# ESP32__20240824.net
KiCad netlist of a schematic drawn in Altium Designer
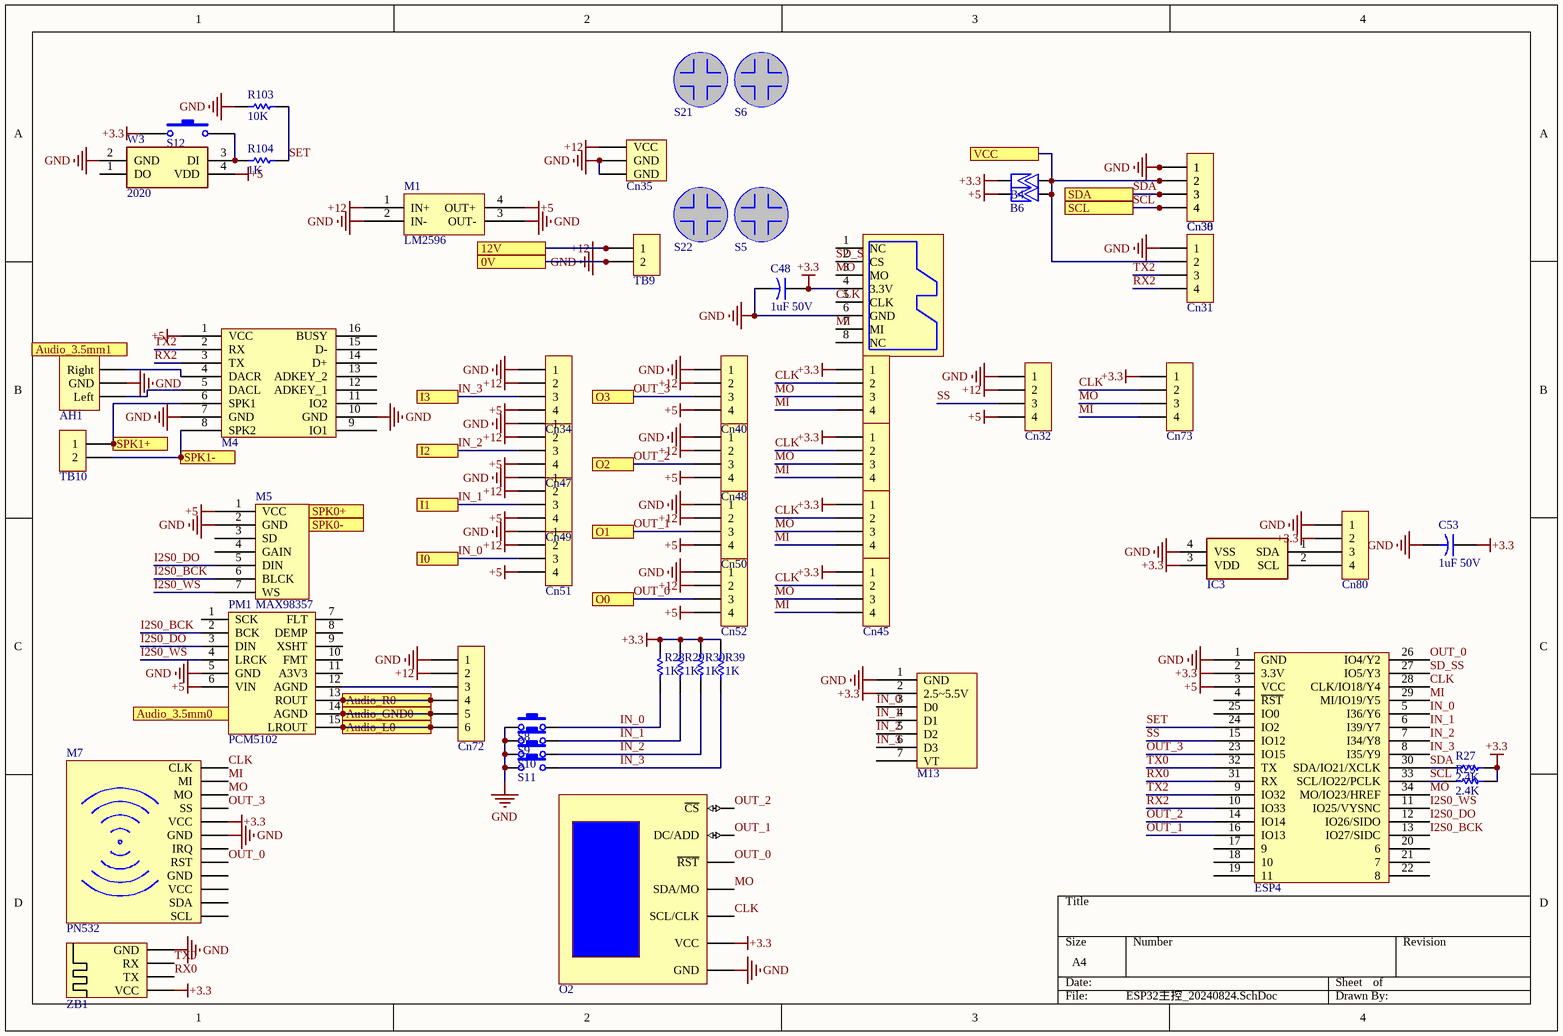
[diagram p0: ESP32主控_20240824.SchDoc]

(export (version "E")
  (design (tool "Eeschema 10.0.6"))
  (components
    (comp (ref "AH1")
      (value "Interface_Audio_hole")
      (footprint "Audio_hole_DIP")
      (description "音源孔")
      (libsource (lib "MyLibray") (part "Interface_Audio_hole"))
    )
    (comp (ref "B4")
      (value "短路")
      (footprint "BYPASS-0805")
      (description "短路焊點(如標註短路則需額外補錫使其短路)")
      (libsource (lib "MyLibray") (part "Bypass"))
    )
    (comp (ref "B6")
      (value "不短路")
      (footprint "BYPASS-0805")
      (description "短路焊點(如標註短路則需額外補錫使其短路)")
      (libsource (lib "MyLibray") (part "Bypass"))
    )
    (comp (ref "C48")
      (value "1uF 50V")
      (footprint "Cap-1206")
      (description "電容")
      (libsource (lib "MyLibray") (part "Cap"))
    )
    (comp (ref "C53")
      (value "1uF 50V")
      (footprint "Cap-1206")
      (description "電容")
      (libsource (lib "MyLibray") (part "Cap"))
    )
    (comp (ref "Cn28")
      (value "KF2510")
      (footprint "Connector_KF2510-4A")
      (description "接線端子")
      (libsource (lib "MyLibray") (part "Contact(4P)"))
    )
    (comp (ref "Cn29")
      (value "KF2510")
      (footprint "Connector_KF2510-4A")
      (description "接線端子")
      (libsource (lib "MyLibray") (part "Contact(4P)"))
    )
    (comp (ref "Cn30")
      (value "KF2510")
      (footprint "Connector_KF2510-4A")
      (description "接線端子")
      (libsource (lib "MyLibray") (part "Contact(4P)"))
    )
    (comp (ref "Cn31")
      (value "KF2510")
      (footprint "Connector_KF2510-4A")
      (description "接線端子")
      (libsource (lib "MyLibray") (part "Contact(4P)"))
    )
    (comp (ref "Cn32")
      (value "KF2510")
      (footprint "Connector_KF2510-4A")
      (description "接線端子")
      (libsource (lib "MyLibray") (part "Contact(4P)"))
    )
    (comp (ref "Cn34")
      (value "KF2510")
      (footprint "Connector_KF2510-4A")
      (description "接線端子")
      (libsource (lib "MyLibray") (part "Contact(4P)"))
    )
    (comp (ref "Cn35")
      (value "DC-005")
      (footprint "Connector_DC-005")
      (description "DC直流接頭")
      (libsource (lib "MyLibray") (part "Contact_DC"))
    )
    (comp (ref "Cn38")
      (value "KF2510")
      (footprint "Connector_KF2510-4A")
      (description "接線端子")
      (libsource (lib "MyLibray") (part "Contact(4P)"))
    )
    (comp (ref "Cn40")
      (value "KF2510")
      (footprint "Connector_KF2510-4A")
      (description "接線端子")
      (libsource (lib "MyLibray") (part "Contact(4P)"))
    )
    (comp (ref "Cn43")
      (value "KF2510")
      (footprint "Connector_KF2510-4A")
      (description "接線端子")
      (libsource (lib "MyLibray") (part "Contact(4P)"))
    )
    (comp (ref "Cn45")
      (value "KF2510")
      (footprint "Connector_KF2510-4A")
      (description "接線端子")
      (libsource (lib "MyLibray") (part "Contact(4P)"))
    )
    (comp (ref "Cn47")
      (value "KF2510")
      (footprint "Connector_KF2510-4A")
      (description "接線端子")
      (libsource (lib "MyLibray") (part "Contact(4P)"))
    )
    (comp (ref "Cn48")
      (value "KF2510")
      (footprint "Connector_KF2510-4A")
      (description "接線端子")
      (libsource (lib "MyLibray") (part "Contact(4P)"))
    )
    (comp (ref "Cn49")
      (value "KF2510")
      (footprint "Connector_KF2510-4A")
      (description "接線端子")
      (libsource (lib "MyLibray") (part "Contact(4P)"))
    )
    (comp (ref "Cn50")
      (value "KF2510")
      (footprint "Connector_KF2510-4A")
      (description "接線端子")
      (libsource (lib "MyLibray") (part "Contact(4P)"))
    )
    (comp (ref "Cn51")
      (value "KF2510")
      (footprint "Connector_KF2510-4A")
      (description "接線端子")
      (libsource (lib "MyLibray") (part "Contact(4P)"))
    )
    (comp (ref "Cn52")
      (value "KF2510")
      (footprint "Connector_KF2510-4A")
      (description "接線端子")
      (libsource (lib "MyLibray") (part "Contact(4P)"))
    )
    (comp (ref "Cn72")
      (value "KF2510-6")
      (footprint "Connector_KF2510-6W")
      (description "接線端子")
      (libsource (lib "MyLibray") (part "Contact(6P)"))
    )
    (comp (ref "Cn73")
      (value "KF2510")
      (footprint "Connector_KF2510-4A")
      (description "接線端子")
      (libsource (lib "MyLibray") (part "Contact(4P)"))
    )
    (comp (ref "Cn80")
      (value "KF2510")
      (footprint "Connector_KF2510-4A")
      (description "接線端子")
      (libsource (lib "MyLibray") (part "Contact(4P)"))
    )
    (comp (ref "ESP4")
      (value "U?")
      (footprint "ESP32-WROVER-CAM Module")
      (description "WIFI通訊模組,帶OV2640攝像頭")
      (libsource (lib "MyModule") (part "ESP32-WROVER-CAM"))
    )
    (comp (ref "IC3")
      (value "SHT40")
      (footprint "Sensor_SHT40")
      (description "I2C,溫溼度感測器")
      (fields (field (name "MANUFACTURER_PART_NUMBER") "SHT40-AD1B-R3"))
      (libsource (lib "MyLibray") (part "Sensor_SHT40-AD1B-R3"))
    )
    (comp (ref "M1")
      (value "LM2596")
      (footprint "LM2596 Module")
      (description "DC to DC 降壓模組")
      (libsource (lib "MyModule") (part "LM2596"))
    )
    (comp (ref "M4")
      (value "BY8001-16P")
      (footprint "BY8001-16P")
      (description "TTL通訊SD卡撥放mp3模組")
      (libsource (lib "MyModule") (part "Mini MP3 Player"))
    )
    (comp (ref "M5")
      (value "MAX98357")
      (footprint "MAX98357_Module")
      (description "I2S音頻直驅模組,3W")
      (libsource (lib "MyModule") (part "MAX98357 Module"))
    )
    (comp (ref "M7")
      (value "PN532")
      (footprint "PN532")
      (description "NFC模組")
      (libsource (lib "MyModule") (part "PN532"))
    )
    (comp (ref "M13")
      (value "XR390")
      (footprint "XR390 Module")
      (description "遙控器模組")
      (libsource (lib "MyModule") (part "XR390"))
    )
    (comp (ref "MS4")
      (value "Interface_MicroSD card slot")
      (footprint "Interface_MicroSD card slot")
      (description "Micro SD 卡座")
      (libsource (lib "MyLibray") (part "Interface_MicroSD card slot"))
    )
    (comp (ref "O2")
      (value "0.96\"")
      (footprint "OLED-SPI/I2C")
      (description "OLED顯示模組")
      (libsource (lib "MyModule") (part "OLED_SPI/I2C"))
    )
    (comp (ref "PM1")
      (value "PCM5102")
      (footprint "PCM5102_MODULE")
      (description "I2S音頻解碼模組")
      (libsource (lib "MyModule") (part "PCM5102"))
    )
    (comp (ref "R23")
      (value "2.4K")
      (footprint "Res-1206")
      (description "電阻")
      (libsource (lib "MyLibray") (part "Res"))
    )
    (comp (ref "R27")
      (value "2.4K")
      (footprint "Res-1206")
      (description "電阻")
      (libsource (lib "MyLibray") (part "Res"))
    )
    (comp (ref "R28")
      (value "1K")
      (footprint "Res-1206")
      (description "電阻")
      (libsource (lib "MyLibray") (part "Res"))
    )
    (comp (ref "R29")
      (value "1K")
      (footprint "Res-1206")
      (description "電阻")
      (libsource (lib "MyLibray") (part "Res"))
    )
    (comp (ref "R30")
      (value "1K")
      (footprint "Res-1206")
      (description "電阻")
      (libsource (lib "MyLibray") (part "Res"))
    )
    (comp (ref "R39")
      (value "1K")
      (footprint "Res-1206")
      (description "電阻")
      (libsource (lib "MyLibray") (part "Res"))
    )
    (comp (ref "R103")
      (value "10K")
      (footprint "Res-1206")
      (description "電阻")
      (libsource (lib "MyLibray") (part "Res"))
    )
    (comp (ref "R104")
      (value "1K")
      (footprint "Res-1206")
      (description "電阻")
      (libsource (lib "MyLibray") (part "Res"))
    )
    (comp (ref "S5")
      (value "M3")
      (footprint "Screw M3")
      (description "螺絲(非焊接元件)")
      (libsource (lib "MyLibray") (part "Screw"))
    )
    (comp (ref "S6")
      (value "M3")
      (footprint "Screw M3")
      (description "螺絲(非焊接元件)")
      (libsource (lib "MyLibray") (part "Screw"))
    )
    (comp (ref "S8")
      (value "Switch")
      (footprint "Switch SMD-3.6*6*2.5")
      (description "開關_按鍵")
      (libsource (lib "MyLibray") (part "Switch"))
    )
    (comp (ref "S9")
      (value "Switch")
      (footprint "Switch SMD-3.6*6*2.5")
      (description "開關_按鍵")
      (libsource (lib "MyLibray") (part "Switch"))
    )
    (comp (ref "S10")
      (value "Switch")
      (footprint "Switch SMD-3.6*6*2.5")
      (description "開關_按鍵")
      (libsource (lib "MyLibray") (part "Switch"))
    )
    (comp (ref "S11")
      (value "Switch")
      (footprint "Switch SMD-3.6*6*2.5")
      (description "開關_按鍵")
      (libsource (lib "MyLibray") (part "Switch"))
    )
    (comp (ref "S12")
      (value "Switch")
      (footprint "Switch SMD-3.6*6*2.5")
      (description "開關_按鍵")
      (libsource (lib "") (part "Switch_1"))
    )
    (comp (ref "S21")
      (value "M3")
      (footprint "Screw M3")
      (description "螺絲(非焊接元件)")
      (libsource (lib "MyLibray") (part "Screw"))
    )
    (comp (ref "S22")
      (value "M3")
      (footprint "Screw M3")
      (description "螺絲(非焊接元件)")
      (libsource (lib "MyLibray") (part "Screw"))
    )
    (comp (ref "TB9")
      (value "ZB25(2P)")
      (footprint "Terminal block(KF2EDGR-5.08 _2P)")
      (description "端子台")
      (libsource (lib "") (part "Terminal block(2P)_1"))
    )
    (comp (ref "TB10")
      (value "ZB25(2P)")
      (footprint "Terminal block(KF2EDGR-5.08 _2P)")
      (description "端子台")
      (libsource (lib "MyLibray") (part "Terminal block(2P)"))
    )
    (comp (ref "W3")
      (value "2020")
      (footprint "LED-WS2812B-5050")
      (description "LED幻彩燈珠")
      (fields (field (name "MANUFACTURER_PART_NUMBER") "4684") (field (name "MOUSER PART NUMBER") "485-4684"))
      (libsource (lib "MyLibray") (part "WS2812B"))
    )
    (comp (ref "ZB1")
      (value "Zigbee")
      (footprint "ZIGBEE")
      (description "無線通訊模組")
      (libsource (lib "MyModule") (part "Zigbee"))
    )
  )
  (nets
    (net (code "1") (name "+3.3") (class "Default")
      (node (ref "B4") (pin "1") (pinfunction "1_1") (pintype "passive"))
      (node (ref "C48") (pin "1") (pinfunction "1_1") (pintype "passive"))
      (node (ref "C53") (pin "1") (pinfunction "1_1") (pintype "passive"))
      (node (ref "Cn28") (pin "1") (pinfunction "1_1") (pintype "passive"))
      (node (ref "Cn29") (pin "1") (pinfunction "1_1") (pintype "passive"))
      (node (ref "Cn43") (pin "1") (pinfunction "1_1") (pintype "passive"))
      (node (ref "Cn45") (pin "1") (pinfunction "1_1") (pintype "passive"))
      (node (ref "Cn73") (pin "1") (pinfunction "1_1") (pintype "passive"))
      (node (ref "Cn80") (pin "2") (pinfunction "2_2") (pintype "passive"))
      (node (ref "ESP4") (pin "2") (pinfunction "3.3V_2") (pintype "passive"))
      (node (ref "IC3") (pin "3") (pinfunction "VDD_3") (pintype "passive"))
      (node (ref "M13") (pin "2") (pinfunction "2.5~5.5V_2") (pintype "passive"))
      (node (ref "M7") (pin "5") (pinfunction "VCC_5") (pintype "passive"))
      (node (ref "MS4") (pin "4") (pinfunction "3.3V_4") (pintype "power_in"))
      (node (ref "O2") (pin "2") (pinfunction "VCC_2") (pintype "power_in"))
      (node (ref "R23") (pin "2") (pinfunction "2_2") (pintype "passive"))
      (node (ref "R27") (pin "2") (pinfunction "2_2") (pintype "passive"))
      (node (ref "R28") (pin "2") (pinfunction "2_2") (pintype "passive"))
      (node (ref "R29") (pin "2") (pinfunction "2_2") (pintype "passive"))
      (node (ref "R30") (pin "2") (pinfunction "2_2") (pintype "passive"))
      (node (ref "R39") (pin "2") (pinfunction "2_2") (pintype "passive"))
      (node (ref "S12") (pin "1") (pinfunction "1_1") (pintype "passive"))
      (node (ref "ZB1") (pin "1") (pinfunction "VCC_1") (pintype "power_in"))
    )
    (net (code "2") (name "+5") (class "Default")
      (node (ref "B6") (pin "1") (pinfunction "1_1") (pintype "passive"))
      (node (ref "Cn32") (pin "4") (pinfunction "4_4") (pintype "passive"))
      (node (ref "Cn34") (pin "4") (pinfunction "4_4") (pintype "passive"))
      (node (ref "Cn40") (pin "4") (pinfunction "4_4") (pintype "passive"))
      (node (ref "Cn47") (pin "4") (pinfunction "4_4") (pintype "passive"))
      (node (ref "Cn48") (pin "4") (pinfunction "4_4") (pintype "passive"))
      (node (ref "Cn49") (pin "4") (pinfunction "4_4") (pintype "passive"))
      (node (ref "Cn50") (pin "4") (pinfunction "4_4") (pintype "passive"))
      (node (ref "Cn51") (pin "4") (pinfunction "4_4") (pintype "passive"))
      (node (ref "Cn52") (pin "4") (pinfunction "4_4") (pintype "passive"))
      (node (ref "ESP4") (pin "3") (pinfunction "VCC_3") (pintype "passive"))
      (node (ref "M1") (pin "4") (pinfunction "OUT+_4") (pintype "passive"))
      (node (ref "M4") (pin "1") (pinfunction "VCC_1") (pintype "passive"))
      (node (ref "M5") (pin "1") (pinfunction "VCC_1") (pintype "passive"))
      (node (ref "PM1") (pin "6") (pinfunction "VIN_6") (pintype "passive"))
      (node (ref "W3") (pin "4") (pinfunction "VDD_4") (pintype "passive"))
    )
    (net (code "3") (name "+12") (class "Default")
      (node (ref "Cn32") (pin "2") (pinfunction "2_2") (pintype "passive"))
      (node (ref "Cn34") (pin "2") (pinfunction "2_2") (pintype "passive"))
      (node (ref "Cn35") (pin "1") (pinfunction "VCC_1") (pintype "passive"))
      (node (ref "Cn40") (pin "2") (pinfunction "2_2") (pintype "passive"))
      (node (ref "Cn47") (pin "2") (pinfunction "2_2") (pintype "passive"))
      (node (ref "Cn48") (pin "2") (pinfunction "2_2") (pintype "passive"))
      (node (ref "Cn49") (pin "2") (pinfunction "2_2") (pintype "passive"))
      (node (ref "Cn50") (pin "2") (pinfunction "2_2") (pintype "passive"))
      (node (ref "Cn51") (pin "2") (pinfunction "2_2") (pintype "passive"))
      (node (ref "Cn52") (pin "2") (pinfunction "2_2") (pintype "passive"))
      (node (ref "Cn72") (pin "2") (pinfunction "2_2") (pintype "passive"))
      (node (ref "M1") (pin "1") (pinfunction "IN+_1") (pintype "passive"))
      (node (ref "TB9") (pin "1") (pinfunction "1_1") (pintype "passive"))
    )
    (net (code "6") (name "/Audio_GND0") (class "Default")
      (node (ref "Cn72") (pin "5") (pinfunction "5_5") (pintype "passive"))
      (node (ref "PM1") (pin "14") (pinfunction "AGND_14") (pintype "passive"))
    )
    (net (code "7") (name "/Audio_L0") (class "Default")
      (node (ref "Cn72") (pin "6") (pinfunction "6_6") (pintype "passive"))
      (node (ref "PM1") (pin "15") (pinfunction "LROUT_15") (pintype "passive"))
    )
    (net (code "8") (name "/Audio_R0") (class "Default")
      (node (ref "Cn72") (pin "4") (pinfunction "4_4") (pintype "passive"))
      (node (ref "PM1") (pin "13") (pinfunction "ROUT_13") (pintype "passive"))
    )
    (net (code "9") (name "/CLK") (class "Default")
      (node (ref "Cn28") (pin "2") (pinfunction "2_2") (pintype "passive"))
      (node (ref "Cn29") (pin "2") (pinfunction "2_2") (pintype "passive"))
      (node (ref "Cn43") (pin "2") (pinfunction "2_2") (pintype "passive"))
      (node (ref "Cn45") (pin "2") (pinfunction "2_2") (pintype "passive"))
      (node (ref "Cn73") (pin "2") (pinfunction "2_2") (pintype "passive"))
      (node (ref "ESP4") (pin "28") (pinfunction "CLK/IO18/Y4_28") (pintype "passive"))
      (node (ref "M7") (pin "1") (pinfunction "CLK_1") (pintype "passive"))
      (node (ref "MS4") (pin "5") (pinfunction "CLK_5") (pintype "passive"))
      (node (ref "O2") (pin "3") (pinfunction "SCL/CLK_3") (pintype "passive"))
    )
    (net (code "10") (name "/I2S0_BCK") (class "Default")
      (node (ref "ESP4") (pin "13") (pinfunction "IO27/SIDC_13") (pintype "passive"))
      (node (ref "M5") (pin "6") (pinfunction "BLCK_6") (pintype "passive"))
      (node (ref "PM1") (pin "2") (pinfunction "BCK_2") (pintype "passive"))
    )
    (net (code "11") (name "/I2S0_DO") (class "Default")
      (node (ref "ESP4") (pin "12") (pinfunction "IO26/SIDO_12") (pintype "passive"))
      (node (ref "M5") (pin "5") (pinfunction "DIN_5") (pintype "passive"))
      (node (ref "PM1") (pin "3") (pinfunction "DIN_3") (pintype "passive"))
    )
    (net (code "12") (name "/I2S0_WS") (class "Default")
      (node (ref "ESP4") (pin "11") (pinfunction "IO25/VYSNC_11") (pintype "passive"))
      (node (ref "M5") (pin "7") (pinfunction "WS_7") (pintype "passive"))
      (node (ref "PM1") (pin "4") (pinfunction "LRCK_4") (pintype "passive"))
    )
    (net (code "13") (name "/IN_0") (class "Default")
      (node (ref "Cn51") (pin "3") (pinfunction "3_3") (pintype "passive"))
      (node (ref "ESP4") (pin "5") (pinfunction "I36/Y6_5") (pintype "passive"))
      (node (ref "M13") (pin "3") (pinfunction "D0_3") (pintype "passive"))
      (node (ref "R28") (pin "1") (pinfunction "1_1") (pintype "passive"))
      (node (ref "S8") (pin "2") (pinfunction "2_2") (pintype "passive"))
    )
    (net (code "14") (name "/IN_1") (class "Default")
      (node (ref "Cn49") (pin "3") (pinfunction "3_3") (pintype "passive"))
      (node (ref "ESP4") (pin "6") (pinfunction "I39/Y7_6") (pintype "passive"))
      (node (ref "M13") (pin "4") (pinfunction "D1_4") (pintype "passive"))
      (node (ref "R29") (pin "1") (pinfunction "1_1") (pintype "passive"))
      (node (ref "S9") (pin "2") (pinfunction "2_2") (pintype "passive"))
    )
    (net (code "15") (name "/IN_2") (class "Default")
      (node (ref "Cn47") (pin "3") (pinfunction "3_3") (pintype "passive"))
      (node (ref "ESP4") (pin "7") (pinfunction "I34/Y8_7") (pintype "passive"))
      (node (ref "M13") (pin "5") (pinfunction "D2_5") (pintype "passive"))
      (node (ref "R30") (pin "1") (pinfunction "1_1") (pintype "passive"))
      (node (ref "S10") (pin "2") (pinfunction "2_2") (pintype "passive"))
    )
    (net (code "16") (name "/IN_3") (class "Default")
      (node (ref "Cn34") (pin "3") (pinfunction "3_3") (pintype "passive"))
      (node (ref "ESP4") (pin "8") (pinfunction "I35/Y9_8") (pintype "passive"))
      (node (ref "M13") (pin "6") (pinfunction "D3_6") (pintype "passive"))
      (node (ref "R39") (pin "1") (pinfunction "1_1") (pintype "passive"))
      (node (ref "S11") (pin "2") (pinfunction "2_2") (pintype "passive"))
    )
    (net (code "17") (name "/MI") (class "Default")
      (node (ref "Cn28") (pin "4") (pinfunction "4_4") (pintype "passive"))
      (node (ref "Cn29") (pin "4") (pinfunction "4_4") (pintype "passive"))
      (node (ref "Cn43") (pin "4") (pinfunction "4_4") (pintype "passive"))
      (node (ref "Cn45") (pin "4") (pinfunction "4_4") (pintype "passive"))
      (node (ref "Cn73") (pin "4") (pinfunction "4_4") (pintype "passive"))
      (node (ref "ESP4") (pin "29") (pinfunction "MI/IO19/Y5_29") (pintype "passive"))
      (node (ref "M7") (pin "2") (pinfunction "MI_2") (pintype "passive"))
      (node (ref "MS4") (pin "7") (pinfunction "MI_7") (pintype "passive"))
    )
    (net (code "18") (name "/MO") (class "Default")
      (node (ref "Cn28") (pin "3") (pinfunction "3_3") (pintype "passive"))
      (node (ref "Cn29") (pin "3") (pinfunction "3_3") (pintype "passive"))
      (node (ref "Cn43") (pin "3") (pinfunction "3_3") (pintype "passive"))
      (node (ref "Cn45") (pin "3") (pinfunction "3_3") (pintype "passive"))
      (node (ref "Cn73") (pin "3") (pinfunction "3_3") (pintype "passive"))
      (node (ref "ESP4") (pin "34") (pinfunction "MO/IO23/HREF_34") (pintype "passive"))
      (node (ref "M7") (pin "3") (pinfunction "MO_3") (pintype "passive"))
      (node (ref "MS4") (pin "3") (pinfunction "MO_3") (pintype "passive"))
      (node (ref "O2") (pin "4") (pinfunction "SDA/MO_4") (pintype "passive"))
    )
    (net (code "19") (name "/OUT_0") (class "Default")
      (node (ref "Cn52") (pin "3") (pinfunction "3_3") (pintype "passive"))
      (node (ref "ESP4") (pin "26") (pinfunction "IO4/Y2_26") (pintype "passive"))
      (node (ref "M7") (pin "8") (pinfunction "RST_8") (pintype "passive"))
      (node (ref "O2") (pin "5") (pinfunction "~{RST}_5") (pintype "passive"))
    )
    (net (code "20") (name "/OUT_1") (class "Default")
      (node (ref "Cn50") (pin "3") (pinfunction "3_3") (pintype "passive"))
      (node (ref "ESP4") (pin "16") (pinfunction "IO13_16") (pintype "passive"))
      (node (ref "O2") (pin "6") (pinfunction "DC/ADD_6") (pintype "bidirectional"))
    )
    (net (code "21") (name "/OUT_2") (class "Default")
      (node (ref "Cn48") (pin "3") (pinfunction "3_3") (pintype "passive"))
      (node (ref "ESP4") (pin "14") (pinfunction "IO14_14") (pintype "passive"))
      (node (ref "O2") (pin "7") (pinfunction "~{CS}_7") (pintype "bidirectional"))
    )
    (net (code "22") (name "/OUT_3") (class "Default")
      (node (ref "Cn40") (pin "3") (pinfunction "3_3") (pintype "passive"))
      (node (ref "ESP4") (pin "23") (pinfunction "IO15_23") (pintype "passive"))
      (node (ref "M7") (pin "4") (pinfunction "SS_4") (pintype "passive"))
    )
    (net (code "23") (name "/RX0") (class "Default")
      (node (ref "ESP4") (pin "31") (pinfunction "RX_31") (pintype "passive"))
      (node (ref "ZB1") (pin "2") (pinfunction "TX_2") (pintype "passive"))
    )
    (net (code "24") (name "/RX2") (class "Default")
      (node (ref "Cn31") (pin "4") (pinfunction "4_4") (pintype "passive"))
      (node (ref "ESP4") (pin "10") (pinfunction "IO33_10") (pintype "passive"))
      (node (ref "M4") (pin "3") (pinfunction "TX_3") (pintype "passive"))
    )
    (net (code "25") (name "/SCL") (class "Default")
      (node (ref "Cn30") (pin "4") (pinfunction "4_4") (pintype "passive"))
      (node (ref "Cn38") (pin "4") (pinfunction "4_4") (pintype "passive"))
      (node (ref "ESP4") (pin "33") (pinfunction "SCL/IO22/PCLK_33") (pintype "passive"))
      (node (ref "R23") (pin "1") (pinfunction "1_1") (pintype "passive"))
    )
    (net (code "26") (name "/SDA") (class "Default")
      (node (ref "Cn30") (pin "3") (pinfunction "3_3") (pintype "passive"))
      (node (ref "Cn38") (pin "3") (pinfunction "3_3") (pintype "passive"))
      (node (ref "ESP4") (pin "30") (pinfunction "SDA/IO21/XCLK_30") (pintype "passive"))
      (node (ref "R27") (pin "1") (pinfunction "1_1") (pintype "passive"))
    )
    (net (code "27") (name "/SD_SS") (class "Default")
      (node (ref "ESP4") (pin "27") (pinfunction "IO5/Y3_27") (pintype "passive"))
      (node (ref "MS4") (pin "2") (pinfunction "CS_2") (pintype "passive"))
    )
    (net (code "28") (name "/SET") (class "Default")
      (node (ref "ESP4") (pin "24") (pinfunction "IO2_24") (pintype "passive"))
      (node (ref "R103") (pin "2") (pinfunction "2_2") (pintype "passive"))
      (node (ref "R104") (pin "2") (pinfunction "2_2") (pintype "passive"))
    )
    (net (code "31") (name "/SPK1+") (class "Default")
      (node (ref "M4") (pin "6") (pinfunction "SPK1_6") (pintype "passive"))
      (node (ref "TB10") (pin "1") (pinfunction "1_1") (pintype "passive"))
    )
    (net (code "32") (name "/SPK1-") (class "Default")
      (node (ref "M4") (pin "8") (pinfunction "SPK2_8") (pintype "passive"))
      (node (ref "TB10") (pin "2") (pinfunction "2_2") (pintype "passive"))
    )
    (net (code "33") (name "/SS") (class "Default")
      (node (ref "Cn32") (pin "3") (pinfunction "3_3") (pintype "passive"))
      (node (ref "ESP4") (pin "15") (pinfunction "IO12_15") (pintype "passive"))
    )
    (net (code "34") (name "/TX0") (class "Default")
      (node (ref "ESP4") (pin "32") (pinfunction "TX_32") (pintype "passive"))
      (node (ref "ZB1") (pin "3") (pinfunction "RX_3") (pintype "passive"))
    )
    (net (code "35") (name "/TX2") (class "Default")
      (node (ref "Cn31") (pin "3") (pinfunction "3_3") (pintype "passive"))
      (node (ref "ESP4") (pin "9") (pinfunction "IO32_9") (pintype "passive"))
      (node (ref "M4") (pin "2") (pinfunction "RX_2") (pintype "passive"))
    )
    (net (code "36") (name "/VCC") (class "Default")
      (node (ref "B4") (pin "2") (pinfunction "2_2") (pintype "passive"))
      (node (ref "B6") (pin "2") (pinfunction "2_2") (pintype "passive"))
      (node (ref "Cn30") (pin "2") (pinfunction "2_2") (pintype "passive"))
      (node (ref "Cn31") (pin "2") (pinfunction "2_2") (pintype "passive"))
      (node (ref "Cn38") (pin "2") (pinfunction "2_2") (pintype "passive"))
    )
    (net (code "37") (name "GND") (class "Default")
      (node (ref "AH1") (pin "1") (pinfunction "GND_1") (pintype "power_in"))
      (node (ref "C48") (pin "2") (pinfunction "2_2") (pintype "passive"))
      (node (ref "C53") (pin "2") (pinfunction "2_2") (pintype "passive"))
      (node (ref "Cn30") (pin "1") (pinfunction "1_1") (pintype "passive"))
      (node (ref "Cn31") (pin "1") (pinfunction "1_1") (pintype "passive"))
      (node (ref "Cn32") (pin "1") (pinfunction "1_1") (pintype "passive"))
      (node (ref "Cn34") (pin "1") (pinfunction "1_1") (pintype "passive"))
      (node (ref "Cn35") (pin "2") (pinfunction "GND_2") (pintype "passive"))
      (node (ref "Cn35") (pin "3") (pinfunction "GND_3") (pintype "passive"))
      (node (ref "Cn38") (pin "1") (pinfunction "1_1") (pintype "passive"))
      (node (ref "Cn40") (pin "1") (pinfunction "1_1") (pintype "passive"))
      (node (ref "Cn47") (pin "1") (pinfunction "1_1") (pintype "passive"))
      (node (ref "Cn48") (pin "1") (pinfunction "1_1") (pintype "passive"))
      (node (ref "Cn49") (pin "1") (pinfunction "1_1") (pintype "passive"))
      (node (ref "Cn50") (pin "1") (pinfunction "1_1") (pintype "passive"))
      (node (ref "Cn51") (pin "1") (pinfunction "1_1") (pintype "passive"))
      (node (ref "Cn52") (pin "1") (pinfunction "1_1") (pintype "passive"))
      (node (ref "Cn72") (pin "1") (pinfunction "1_1") (pintype "passive"))
      (node (ref "Cn80") (pin "1") (pinfunction "1_1") (pintype "passive"))
      (node (ref "ESP4") (pin "1") (pinfunction "GND_1") (pintype "passive"))
      (node (ref "IC3") (pin "4") (pinfunction "VSS_4") (pintype "passive"))
      (node (ref "M1") (pin "2") (pinfunction "IN-_2") (pintype "passive"))
      (node (ref "M1") (pin "3") (pinfunction "OUT-_3") (pintype "passive"))
      (node (ref "M13") (pin "1") (pinfunction "GND_1") (pintype "passive"))
      (node (ref "M4") (pin "10") (pinfunction "GND_10") (pintype "passive"))
      (node (ref "M4") (pin "7") (pinfunction "GND_7") (pintype "passive"))
      (node (ref "M5") (pin "2") (pinfunction "GND_2") (pintype "passive"))
      (node (ref "M7") (pin "6") (pinfunction "GND_6") (pintype "passive"))
      (node (ref "MS4") (pin "6") (pinfunction "GND_6") (pintype "power_in"))
      (node (ref "O2") (pin "1") (pinfunction "GND_1") (pintype "power_in"))
      (node (ref "PM1") (pin "5") (pinfunction "GND_5") (pintype "passive"))
      (node (ref "R103") (pin "1") (pinfunction "1_1") (pintype "passive"))
      (node (ref "S10") (pin "1") (pinfunction "1_1") (pintype "passive"))
      (node (ref "S11") (pin "1") (pinfunction "1_1") (pintype "passive"))
      (node (ref "S8") (pin "1") (pinfunction "1_1") (pintype "passive"))
      (node (ref "S9") (pin "1") (pinfunction "1_1") (pintype "passive"))
      (node (ref "TB9") (pin "2") (pinfunction "2_2") (pintype "passive"))
      (node (ref "W3") (pin "2") (pinfunction "GND_2") (pintype "passive"))
      (node (ref "ZB1") (pin "4") (pinfunction "GND_4") (pintype "power_in"))
    )
    (net (code "38") (name "Net-(AH1-Left)") (class "Default")
      (node (ref "AH1") (pin "2") (pinfunction "Left_2") (pintype "passive"))
      (node (ref "M4") (pin "5") (pinfunction "DACL_5") (pintype "passive"))
    )
    (net (code "39") (name "Net-(AH1-Right)") (class "Default")
      (node (ref "AH1") (pin "3") (pinfunction "Right_3") (pintype "passive"))
      (node (ref "M4") (pin "4") (pinfunction "DACR_4") (pintype "passive"))
    )
    (net (code "40") (name "Net-(Cn72-Pad3)") (class "Default")
      (node (ref "Cn72") (pin "3") (pinfunction "3_3") (pintype "passive"))
      (node (ref "PM1") (pin "12") (pinfunction "AGND_12") (pintype "passive"))
    )
    (net (code "41") (name "Net-(IC3-SCL)") (class "Default")
      (node (ref "Cn80") (pin "4") (pinfunction "4_4") (pintype "passive"))
      (node (ref "IC3") (pin "2") (pinfunction "SCL_2") (pintype "passive"))
    )
    (net (code "42") (name "Net-(IC3-SDA)") (class "Default")
      (node (ref "Cn80") (pin "3") (pinfunction "3_3") (pintype "passive"))
      (node (ref "IC3") (pin "1") (pinfunction "SDA_1") (pintype "passive"))
    )
    (net (code "43") (name "Net-(W3-DI)") (class "Default")
      (node (ref "R104") (pin "1") (pinfunction "1_1") (pintype "passive"))
      (node (ref "S12") (pin "2") (pinfunction "2_2") (pintype "passive"))
      (node (ref "W3") (pin "3") (pinfunction "DI_3") (pintype "passive"))
    )
    (net (code "44") (name "unconnected-(ESP4-6-Pad20)") (class "Default")
      (node (ref "ESP4") (pin "20") (pinfunction "6_20") (pintype "passive"))
    )
    (net (code "45") (name "unconnected-(ESP4-7-Pad21)") (class "Default")
      (node (ref "ESP4") (pin "21") (pinfunction "7_21") (pintype "passive"))
    )
    (net (code "46") (name "unconnected-(ESP4-8-Pad22)") (class "Default")
      (node (ref "ESP4") (pin "22") (pinfunction "8_22") (pintype "passive"))
    )
    (net (code "47") (name "unconnected-(ESP4-9-Pad17)") (class "Default")
      (node (ref "ESP4") (pin "17") (pinfunction "9_17") (pintype "passive"))
    )
    (net (code "48") (name "unconnected-(ESP4-10-Pad18)") (class "Default")
      (node (ref "ESP4") (pin "18") (pinfunction "10_18") (pintype "passive"))
    )
    (net (code "49") (name "unconnected-(ESP4-11-Pad19)") (class "Default")
      (node (ref "ESP4") (pin "19") (pinfunction "11_19") (pintype "passive"))
    )
    (net (code "50") (name "unconnected-(ESP4-IO0-Pad25)") (class "Default")
      (node (ref "ESP4") (pin "25") (pinfunction "IO0_25") (pintype "passive"))
    )
    (net (code "51") (name "unconnected-(ESP4-~{RST}-Pad4)") (class "Default")
      (node (ref "ESP4") (pin "4") (pinfunction "~{RST}_4") (pintype "passive"))
    )
    (net (code "52") (name "unconnected-(M4-ADKEY_1-Pad12)") (class "Default")
      (node (ref "M4") (pin "12") (pinfunction "ADKEY_1_12") (pintype "passive"))
    )
    (net (code "53") (name "unconnected-(M4-ADKEY_2-Pad13)") (class "Default")
      (node (ref "M4") (pin "13") (pinfunction "ADKEY_2_13") (pintype "passive"))
    )
    (net (code "54") (name "unconnected-(M4-BUSY-Pad16)") (class "Default")
      (node (ref "M4") (pin "16") (pinfunction "BUSY_16") (pintype "passive"))
    )
    (net (code "55") (name "unconnected-(M4-D+-Pad14)") (class "Default")
      (node (ref "M4") (pin "14") (pinfunction "D+_14") (pintype "passive"))
    )
    (net (code "56") (name "unconnected-(M4-D--Pad15)") (class "Default")
      (node (ref "M4") (pin "15") (pinfunction "D-_15") (pintype "passive"))
    )
    (net (code "57") (name "unconnected-(M4-IO1-Pad9)") (class "Default")
      (node (ref "M4") (pin "9") (pinfunction "IO1_9") (pintype "passive"))
    )
    (net (code "58") (name "unconnected-(M4-IO2-Pad11)") (class "Default")
      (node (ref "M4") (pin "11") (pinfunction "IO2_11") (pintype "passive"))
    )
    (net (code "59") (name "unconnected-(M5-GAIN-Pad4)") (class "Default")
      (node (ref "M5") (pin "4") (pinfunction "GAIN_4") (pintype "passive"))
    )
    (net (code "60") (name "unconnected-(M5-SD-Pad3)") (class "Default")
      (node (ref "M5") (pin "3") (pinfunction "SD_3") (pintype "passive"))
    )
    (net (code "61") (name "unconnected-(M7-GND-Pad9)") (class "Default")
      (node (ref "M7") (pin "9") (pinfunction "GND_9") (pintype "passive"))
    )
    (net (code "62") (name "unconnected-(M7-IRQ-Pad7)") (class "Default")
      (node (ref "M7") (pin "7") (pinfunction "IRQ_7") (pintype "passive"))
    )
    (net (code "63") (name "unconnected-(M7-SCL-Pad12)") (class "Default")
      (node (ref "M7") (pin "12") (pinfunction "SCL_12") (pintype "passive"))
    )
    (net (code "64") (name "unconnected-(M7-SDA-Pad11)") (class "Default")
      (node (ref "M7") (pin "11") (pinfunction "SDA_11") (pintype "passive"))
    )
    (net (code "65") (name "unconnected-(M7-VCC-Pad10)") (class "Default")
      (node (ref "M7") (pin "10") (pinfunction "VCC_10") (pintype "passive"))
    )
    (net (code "66") (name "unconnected-(M13-VT-Pad7)") (class "Default")
      (node (ref "M13") (pin "7") (pinfunction "VT_7") (pintype "passive"))
    )
    (net (code "67") (name "unconnected-(MS4-NC-Pad1)") (class "Default")
      (node (ref "MS4") (pin "1") (pinfunction "NC_1") (pintype "passive"))
    )
    (net (code "68") (name "unconnected-(MS4-NC-Pad8)") (class "Default")
      (node (ref "MS4") (pin "8") (pinfunction "NC_8") (pintype "passive"))
    )
    (net (code "69") (name "unconnected-(PM1-A3V3-Pad11)") (class "Default")
      (node (ref "PM1") (pin "11") (pinfunction "A3V3_11") (pintype "passive"))
    )
    (net (code "70") (name "unconnected-(PM1-DEMP-Pad8)") (class "Default")
      (node (ref "PM1") (pin "8") (pinfunction "DEMP_8") (pintype "passive"))
    )
    (net (code "71") (name "unconnected-(PM1-FLT-Pad7)") (class "Default")
      (node (ref "PM1") (pin "7") (pinfunction "FLT_7") (pintype "passive"))
    )
    (net (code "72") (name "unconnected-(PM1-FMT-Pad10)") (class "Default")
      (node (ref "PM1") (pin "10") (pinfunction "FMT_10") (pintype "passive"))
    )
    (net (code "73") (name "unconnected-(PM1-SCK-Pad1)") (class "Default")
      (node (ref "PM1") (pin "1") (pinfunction "SCK_1") (pintype "passive"))
    )
    (net (code "74") (name "unconnected-(PM1-XSHT-Pad9)") (class "Default")
      (node (ref "PM1") (pin "9") (pinfunction "XSHT_9") (pintype "passive"))
    )
    (net (code "75") (name "unconnected-(W3-DO-Pad1)") (class "Default")
      (node (ref "W3") (pin "1") (pinfunction "DO_1") (pintype "passive"))
    )
  )
)
